# Sheet1.net
KiCad netlist of a schematic drawn in Altium Designer
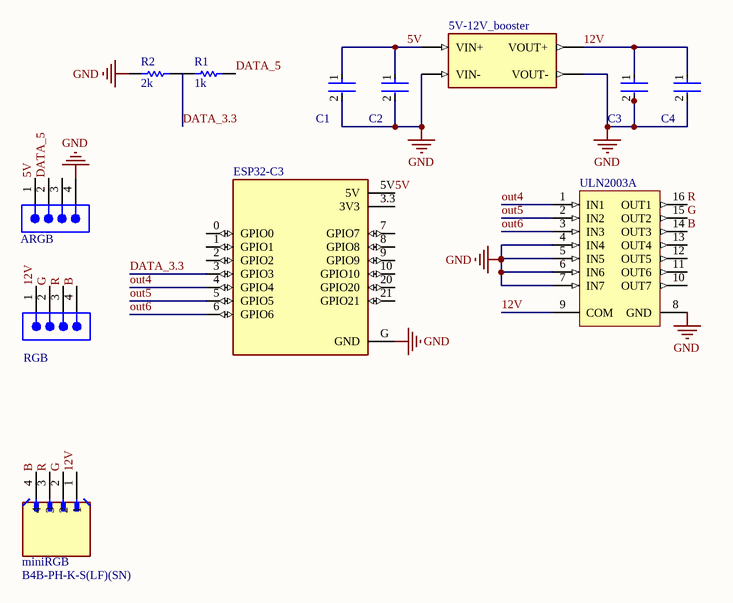
[diagram p0: Sheet1.SchDoc]

(export (version "E")
  (design (tool "Eeschema 10.0.6"))
  (components
    (comp (ref "5V-12V_booster")
      (value "MT3608_DC-DC_STEP_UP_CONVERTER_2A_BOOSTER_MODULE")
      (footprint "MODULE_MT3608_DC-DC_STEP_UP_CONVERTER_2A_BOOSTER_MODULE")
      (fields
        (field (name "MF") "Generic")
        (field (name "MP") "MT3608 DC-DC Step Up Converter 2A Booster Module")
      )
      (libsource (lib "MT3608_DC-DC_STEP_UP_CONVERTER_2A_BOOSTER_MODULE") (part "MT3608_DC-DC_STEP_UP_CONVERTER_2A_BOOSTER_MODULE"))
    )
    (comp (ref "ARGB")
      (value "TSW-104-08-T-S")
      (footprint "SMTC-TSW-104-08-X-S")
      (description "0.025\" SQ Post Header, Through-hole, Vertical, -55 to 105 degC, 2.54 mm Pitch, 4-Pin, Male, RoHS")
      (fields (field (name "MANUFACTURER") "Samtec"))
      (libsource (lib "Altium Content Vault") (part "SMTC-TSW-104-08-X-S"))
    )
    (comp (ref "C1")
      (value "200nF")
      (footprint "FP-RDE2M1-MFG")
      (description "Ceramic Capacitor 10nF ±10% 630V X7R Radial")
      (fields (field (name "TOLERANCE") "10%"))
      (libsource (lib "Altium Content Vault") (part "b4654b650e69147ec39a6b967a45e02"))
    )
    (comp (ref "C2")
      (value "200nF")
      (footprint "FP-RDE2M1-MFG")
      (description "Ceramic Capacitor 10nF ±10% 630V X7R Radial")
      (fields (field (name "TOLERANCE") "10%"))
      (libsource (lib "Altium Content Vault") (part "b4654b650e69147ec39a6b967a45e02"))
    )
    (comp (ref "C3")
      (value "200nF")
      (footprint "FP-RDE2M1-MFG")
      (description "Ceramic Capacitor 10nF ±10% 630V X7R Radial")
      (fields (field (name "TOLERANCE") "10%"))
      (libsource (lib "Altium Content Vault") (part "b4654b650e69147ec39a6b967a45e02"))
    )
    (comp (ref "C4")
      (value "200nF")
      (footprint "FP-RDE2M1-MFG")
      (description "Ceramic Capacitor 10nF ±10% 630V X7R Radial")
      (fields (field (name "TOLERANCE") "10%"))
      (libsource (lib "Altium Content Vault") (part "b4654b650e69147ec39a6b967a45e02"))
    )
    (comp (ref "ESP32-C3")
      (value "ESP32-C3_SUPERMINI_SMD")
      (footprint "MODULE_ESP32-C3_SUPERMINI")
      (description "Super tiny ESP32-C3 board")
      (fields (field (name "MF") "Espressif Systems") (field (name "MP") "ESP32-C3 SuperMini_SMD"))
      (libsource (lib "ESP32-C3_SUPERMINI_SMD") (part "ESP32-C3_SUPERMINI_SMD"))
    )
    (comp (ref "miniRGB")
      (value "B4B-PH-K-S(LF)(SN)")
      (footprint "JST_B4B-PH-K-S(LF)(SN)")
      (description "Connector Header Through Hole 4 position 0.079 (2.00mm)")
      (fields (field (name "MF") "JST Sales") (field (name "MP") "B4B-PH-K-S (LF)(SN)"))
      (libsource (lib "B4B-PH-K-S_LF__SN_") (part "B4B-PH-K-S(LF)(SN)"))
    )
    (comp (ref "R1")
      (value "1k")
      (footprint "AXIAL-0.3")
      (description "Resistor")
      (fields (field (name "PUBLISHER") "Altium Limited"))
      (libsource (lib "Miscellaneous Devices") (part "Res1"))
    )
    (comp (ref "R2")
      (value "2k")
      (footprint "AXIAL-0.3")
      (description "Resistor")
      (fields (field (name "PUBLISHER") "Altium Limited"))
      (libsource (lib "Miscellaneous Devices") (part "Res1"))
    )
    (comp (ref "RGB")
      (value "ARGB")
      (footprint "SMTC-TSW-104-08-X-S")
      (description "0.025\" SQ Post Header, Through-hole, Vertical, -55 to 105 degC, 2.54 mm Pitch, 4-Pin, Male, RoHS")
      (fields (field (name "PARTNUMBER") "TSW-104-08-T-S") (field (name "MANUFACTURER") "Samtec"))
      (libsource (lib "Altium Content Vault") (part "SMTC-TSW-104-08-X-S"))
    )
    (comp (ref "ULN2003A")
      (value "ULN2003A")
      (footprint "STM-DIP-16L")
      (description "Seven Darlington Array, 50 V, 0.5 A, -40 to 85 degC, 16-Pin DIP, RoHS, Tube")
      (fields (field (name "MANUFACTURER") "STMicroelectronics"))
      (libsource (lib "Altium Content Vault") (part "STM-ULN2003A-PDIP-16"))
    )
  )
  (nets
    (net (code "1") (name "/5V") (class "Default")
      (node (ref "5V-12V_booster") (pin "VIN_P") (pinfunction "VIN+_VIN_P") (pintype "input"))
      (node (ref "ARGB") (pin "1") (pinfunction "1_1") (pintype "passive"))
      (node (ref "C1") (pin "1") (pinfunction "1_1") (pintype "passive"))
      (node (ref "C2") (pin "1") (pinfunction "1_1") (pintype "passive"))
      (node (ref "ESP32-C3") (pin "5V") (pinfunction "5V_5V") (pintype "power_in"))
    )
    (net (code "2") (name "/12V") (class "Default")
      (node (ref "5V-12V_booster") (pin "VOUT_P") (pinfunction "VOUT+_VOUT_P") (pintype "output"))
      (node (ref "C3") (pin "1") (pinfunction "1_1") (pintype "passive"))
      (node (ref "C4") (pin "1") (pinfunction "1_1") (pintype "passive"))
      (node (ref "RGB") (pin "1") (pinfunction "1_1") (pintype "passive"))
      (node (ref "ULN2003A") (pin "9") (pinfunction "COM_9") (pintype "passive"))
      (node (ref "miniRGB") (pin "1") (pinfunction "1_1") (pintype "passive"))
    )
    (net (code "3") (name "/B") (class "Default")
      (node (ref "RGB") (pin "4") (pinfunction "4_4") (pintype "passive"))
      (node (ref "ULN2003A") (pin "14") (pinfunction "OUT3_14") (pintype "output"))
      (node (ref "miniRGB") (pin "4") (pinfunction "4_4") (pintype "passive"))
    )
    (net (code "4") (name "/DATA_3.3") (class "Default")
      (node (ref "ESP32-C3") (pin "3") (pinfunction "GPIO3_3") (pintype "bidirectional"))
      (node (ref "R2") (pin "1") (pinfunction "1_1") (pintype "passive"))
    )
    (net (code "5") (name "/DATA_5") (class "Default")
      (node (ref "ARGB") (pin "2") (pinfunction "2_2") (pintype "passive"))
      (node (ref "R1") (pin "1") (pinfunction "1_1") (pintype "passive"))
    )
    (net (code "6") (name "/G") (class "Default")
      (node (ref "RGB") (pin "2") (pinfunction "2_2") (pintype "passive"))
      (node (ref "ULN2003A") (pin "15") (pinfunction "OUT2_15") (pintype "output"))
      (node (ref "miniRGB") (pin "2") (pinfunction "2_2") (pintype "passive"))
    )
    (net (code "7") (name "/R") (class "Default")
      (node (ref "RGB") (pin "3") (pinfunction "3_3") (pintype "passive"))
      (node (ref "ULN2003A") (pin "16") (pinfunction "OUT1_16") (pintype "output"))
      (node (ref "miniRGB") (pin "3") (pinfunction "3_3") (pintype "passive"))
    )
    (net (code "8") (name "/out4") (class "Default")
      (node (ref "ESP32-C3") (pin "4") (pinfunction "GPIO4_4") (pintype "bidirectional"))
      (node (ref "ULN2003A") (pin "1") (pinfunction "IN1_1") (pintype "input"))
    )
    (net (code "9") (name "/out5") (class "Default")
      (node (ref "ESP32-C3") (pin "5") (pinfunction "GPIO5_5") (pintype "bidirectional"))
      (node (ref "ULN2003A") (pin "2") (pinfunction "IN2_2") (pintype "input"))
    )
    (net (code "10") (name "/out6") (class "Default")
      (node (ref "ESP32-C3") (pin "6") (pinfunction "GPIO6_6") (pintype "bidirectional"))
      (node (ref "ULN2003A") (pin "3") (pinfunction "IN3_3") (pintype "input"))
    )
    (net (code "11") (name "GND") (class "Default")
      (node (ref "5V-12V_booster") (pin "VIN_N") (pinfunction "VIN-_VIN_N") (pintype "input"))
      (node (ref "5V-12V_booster") (pin "VOUT_N") (pinfunction "VOUT-_VOUT_N") (pintype "output"))
      (node (ref "ARGB") (pin "4") (pinfunction "4_4") (pintype "passive"))
      (node (ref "C1") (pin "2") (pinfunction "2_2") (pintype "passive"))
      (node (ref "C2") (pin "2") (pinfunction "2_2") (pintype "passive"))
      (node (ref "C3") (pin "2") (pinfunction "2_2") (pintype "passive"))
      (node (ref "C4") (pin "2") (pinfunction "2_2") (pintype "passive"))
      (node (ref "ESP32-C3") (pin "G") (pinfunction "GND_G") (pintype "power_in"))
      (node (ref "R2") (pin "2") (pinfunction "2_2") (pintype "passive"))
      (node (ref "ULN2003A") (pin "4") (pinfunction "IN4_4") (pintype "input"))
      (node (ref "ULN2003A") (pin "5") (pinfunction "IN5_5") (pintype "input"))
      (node (ref "ULN2003A") (pin "6") (pinfunction "IN6_6") (pintype "input"))
      (node (ref "ULN2003A") (pin "7") (pinfunction "IN7_7") (pintype "input"))
      (node (ref "ULN2003A") (pin "8") (pinfunction "GND_8") (pintype "power_in"))
    )
    (net (code "12") (name "unconnected-(ARGB-Pad3)") (class "Default")
      (node (ref "ARGB") (pin "3") (pinfunction "3_3") (pintype "passive"))
    )
    (net (code "13") (name "unconnected-(ESP32-C3-3V3-Pad3.3)") (class "Default")
      (node (ref "ESP32-C3") (pin "3.3") (pinfunction "3V3_3.3") (pintype "power_in"))
    )
    (net (code "14") (name "unconnected-(ESP32-C3-GPIO0-Pad0)") (class "Default")
      (node (ref "ESP32-C3") (pin "0") (pinfunction "GPIO0_0") (pintype "bidirectional"))
    )
    (net (code "15") (name "unconnected-(ESP32-C3-GPIO1-Pad1)") (class "Default")
      (node (ref "ESP32-C3") (pin "1") (pinfunction "GPIO1_1") (pintype "bidirectional"))
    )
    (net (code "16") (name "unconnected-(ESP32-C3-GPIO2-Pad2)") (class "Default")
      (node (ref "ESP32-C3") (pin "2") (pinfunction "GPIO2_2") (pintype "bidirectional"))
    )
    (net (code "17") (name "unconnected-(ESP32-C3-GPIO7-Pad7)") (class "Default")
      (node (ref "ESP32-C3") (pin "7") (pinfunction "GPIO7_7") (pintype "bidirectional"))
    )
    (net (code "18") (name "unconnected-(ESP32-C3-GPIO8-Pad8)") (class "Default")
      (node (ref "ESP32-C3") (pin "8") (pinfunction "GPIO8_8") (pintype "bidirectional"))
    )
    (net (code "19") (name "unconnected-(ESP32-C3-GPIO9-Pad9)") (class "Default")
      (node (ref "ESP32-C3") (pin "9") (pinfunction "GPIO9_9") (pintype "bidirectional"))
    )
    (net (code "20") (name "unconnected-(ESP32-C3-GPIO10-Pad10)") (class "Default")
      (node (ref "ESP32-C3") (pin "10") (pinfunction "GPIO10_10") (pintype "bidirectional"))
    )
    (net (code "21") (name "unconnected-(ESP32-C3-GPIO20-Pad20)") (class "Default")
      (node (ref "ESP32-C3") (pin "20") (pinfunction "GPIO20_20") (pintype "bidirectional"))
    )
    (net (code "22") (name "unconnected-(ESP32-C3-GPIO21-Pad21)") (class "Default")
      (node (ref "ESP32-C3") (pin "21") (pinfunction "GPIO21_21") (pintype "bidirectional"))
    )
    (net (code "23") (name "unconnected-(R1-Pad2)") (class "Default")
      (node (ref "R1") (pin "2") (pinfunction "2_2") (pintype "passive"))
    )
    (net (code "24") (name "unconnected-(ULN2003A-OUT4-Pad13)") (class "Default")
      (node (ref "ULN2003A") (pin "13") (pinfunction "OUT4_13") (pintype "output"))
    )
    (net (code "25") (name "unconnected-(ULN2003A-OUT5-Pad12)") (class "Default")
      (node (ref "ULN2003A") (pin "12") (pinfunction "OUT5_12") (pintype "output"))
    )
    (net (code "26") (name "unconnected-(ULN2003A-OUT6-Pad11)") (class "Default")
      (node (ref "ULN2003A") (pin "11") (pinfunction "OUT6_11") (pintype "output"))
    )
    (net (code "27") (name "unconnected-(ULN2003A-OUT7-Pad10)") (class "Default")
      (node (ref "ULN2003A") (pin "10") (pinfunction "OUT7_10") (pintype "output"))
    )
  )
)
